# ST_LINK_V2-1.net
KiCad netlist of a schematic drawn in Altium Designer
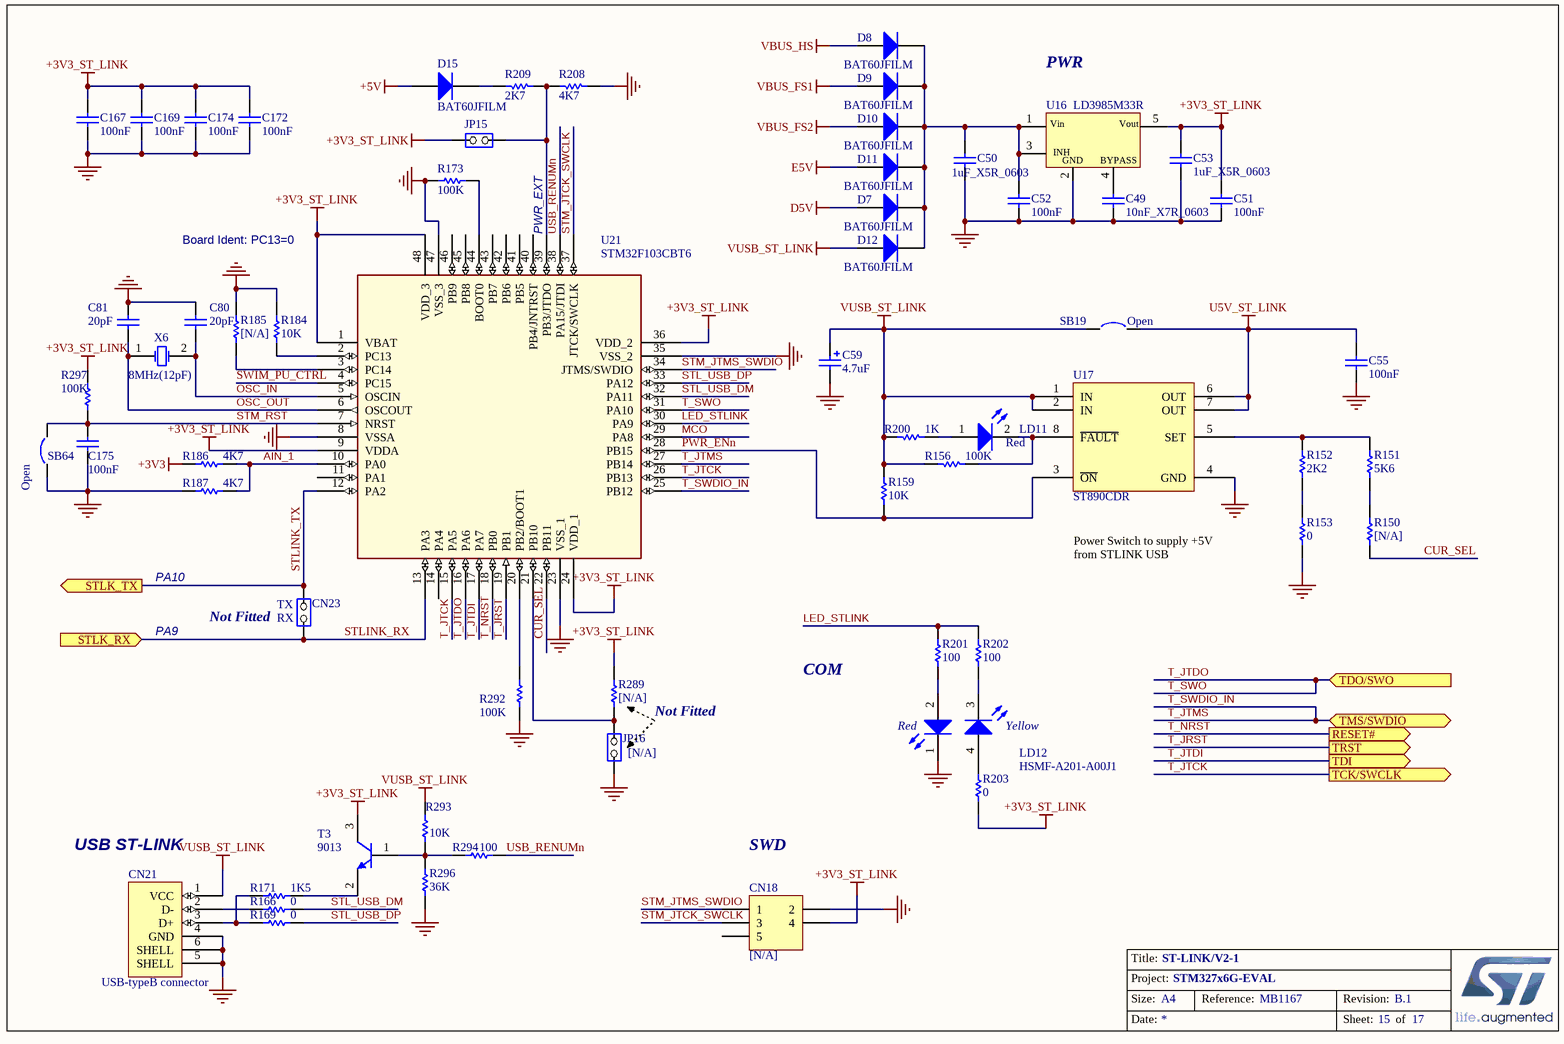
[diagram p0: ST_LINK_V2-1.SCHDOC]

(export (version "E")
  (design (tool "Eeschema 10.0.6"))
  (components
    (comp (ref "C49")
      (value "10nF_X7R_0603")
      (footprint "0603C")
      (description "0603  X7R 10NF")
      (fields (field (name "TOLERANCE") "10%"))
      (libsource (lib "MB963_1") (part "CAP SMD 0603  X7R 10000PF 50V 10%"))
    )
    (comp (ref "C50")
      (value "1uF_X5R_0603")
      (footprint "0603C")
      (description "0603  X5R 1µF")
      (fields (field (name "TOLERANCE") "10%"))
      (libsource (lib "MB963_1") (part "CAP SMD 0603  X5R 1µF 25V 10%"))
    )
    (comp (ref "C51")
      (value "100nF")
      (footprint "0603C")
      (description "Capacitor 0402 / 0603 / 0805")
      (libsource (lib "MCD_TOOLS") (part "Capacitor_ST"))
    )
    (comp (ref "C52")
      (value "100nF")
      (footprint "0603C")
      (description "Capacitor 0402 / 0603 / 0805")
      (libsource (lib "MCD_TOOLS") (part "Capacitor_ST"))
    )
    (comp (ref "C53")
      (value "1uF_X5R_0603")
      (footprint "0603C")
      (description "0603  X5R 1µF")
      (fields (field (name "TOLERANCE") "10%"))
      (libsource (lib "MB963_1") (part "CAP SMD 0603  X5R 1µF 25V 10%"))
    )
    (comp (ref "C55")
      (value "100nF")
      (footprint "0603C")
      (description "Capacitor 0402 / 0603 / 0805")
      (libsource (lib "MCD_TOOLS") (part "Capacitor_ST"))
    )
    (comp (ref "C59")
      (value "4.7uF")
      (footprint "TAN-A")
      (description "Polarized Capacitor (Radial)")
      (fields (field (name "PUBLISHER") "Altium Limited"))
      (libsource (lib "*") (part "Cap Pol1"))
    )
    (comp (ref "C80")
      (value "20pF")
      (footprint "0603C")
      (description "Capacitor 0402 / 0603 / 0805")
      (libsource (lib "MCD_TOOLS") (part "Capacitor_ST"))
    )
    (comp (ref "C81")
      (value "20pF")
      (footprint "0603C")
      (description "Capacitor 0402 / 0603 / 0805")
      (libsource (lib "MCD_TOOLS") (part "Capacitor_ST"))
    )
    (comp (ref "C167")
      (value "100nF")
      (footprint "0603C")
      (description "Capacitor 0402 / 0603 / 0805")
      (libsource (lib "MCD_TOOLS") (part "Capacitor_ST"))
    )
    (comp (ref "C169")
      (value "100nF")
      (footprint "0603C")
      (description "Capacitor 0402 / 0603 / 0805")
      (libsource (lib "MCD_TOOLS") (part "Capacitor_ST"))
    )
    (comp (ref "C172")
      (value "100nF")
      (footprint "0603C")
      (description "Capacitor 0402 / 0603 / 0805")
      (libsource (lib "MCD_TOOLS") (part "Capacitor_ST"))
    )
    (comp (ref "C174")
      (value "100nF")
      (footprint "0603C")
      (description "Capacitor 0402 / 0603 / 0805")
      (libsource (lib "MCD_TOOLS") (part "Capacitor_ST"))
    )
    (comp (ref "C175")
      (value "100nF")
      (footprint "0603C")
      (description "Capacitor 0402 / 0603 / 0805")
      (libsource (lib "MCD_TOOLS") (part "Capacitor_ST"))
    )
    (comp (ref "CN18")
      (value "[N/A]")
      (footprint "HDR_2X3-1_2R54-6")
      (description "Header, 3-Pin, Dual row")
      (fields (field (name "PUBLISHER") "Altium Limited"))
      (libsource (lib "Miscellaneous Connectors") (part "Header 3X2"))
    )
    (comp (ref "CN21")
      (value "USB-typeB connector")
      (footprint "USB-B")
      (libsource (lib "mb1045") (part "USB-typeB connector"))
    )
    (comp (ref "CN23") (value "~") (footprint "SIP2") (libsource (lib "MCD_TOOLS") (part "JP2")))
    (comp (ref "D7")
      (value "BAT60JFILM")
      (footprint "SOD-323")
      (libsource (lib "MCD_TOOLS") (part "BAT60JFILM"))
    )
    (comp (ref "D8")
      (value "BAT60JFILM")
      (footprint "SOD-323")
      (libsource (lib "MCD_TOOLS") (part "BAT60JFILM"))
    )
    (comp (ref "D9")
      (value "BAT60JFILM")
      (footprint "SOD-323")
      (libsource (lib "MCD_TOOLS") (part "BAT60JFILM"))
    )
    (comp (ref "D10")
      (value "BAT60JFILM")
      (footprint "SOD-323")
      (libsource (lib "MCD_TOOLS") (part "BAT60JFILM"))
    )
    (comp (ref "D11")
      (value "BAT60JFILM")
      (footprint "SOD-323")
      (libsource (lib "MCD_TOOLS") (part "BAT60JFILM"))
    )
    (comp (ref "D12")
      (value "BAT60JFILM")
      (footprint "SOD-323")
      (libsource (lib "MCD_TOOLS") (part "BAT60JFILM"))
    )
    (comp (ref "D15")
      (value "BAT60JFILM")
      (footprint "SOD-323")
      (description "Default Diode")
      (fields (field (name "PUBLISHER") "Altium Limited"))
      (libsource (lib "MB1144_1") (part "Diode"))
    )
    (comp (ref "JP15") (value "~") (footprint "SIP2") (libsource (lib "*") (part "JP2")))
    (comp (ref "JP16") (value "[N/A]") (footprint "SIP2") (libsource (lib "*") (part "JP2")))
    (comp (ref "LD11")
      (value "Red")
      (footprint "0603D")
      (description "Typical RED, GREEN, YELLOW, AMBER GaAs LED")
      (fields (field (name "PUBLISHER") "Altium Limited"))
      (libsource (lib "Miscellaneous Devices") (part "LED2"))
    )
    (comp (ref "LD12")
      (value "HSMF-A201-A00J1")
      (footprint "LED2_3528")
      (libsource (lib "MB819") (part "HSMF-A201-A00J1"))
    )
    (comp (ref "R150")
      (value "[N/A]")
      (footprint "0603R")
      (description "Resistor")
      (fields (field (name "PUBLISHER") "Altium Limited"))
      (libsource (lib "") (part "Res1_2"))
    )
    (comp (ref "R151")
      (value "5K6")
      (footprint "0402R")
      (description "Resistor 0402 or 0603 or 0805")
      (libsource (lib "MCD_TOOLS") (part "Resistor_ST"))
    )
    (comp (ref "R152")
      (value "2K2")
      (footprint "0402R")
      (description "Resistor 0402 or 0603 or 0805")
      (libsource (lib "MCD_TOOLS") (part "Resistor_ST"))
    )
    (comp (ref "R153")
      (value "0")
      (footprint "0603R")
      (description "Resistor")
      (fields (field (name "PUBLISHER") "Altium Limited"))
      (libsource (lib "") (part "Res1_2"))
    )
    (comp (ref "R156")
      (value "100K")
      (footprint "0603R")
      (description "Resistor")
      (fields (field (name "PUBLISHER") "Altium Limited"))
      (libsource (lib "*") (part "Res1"))
    )
    (comp (ref "R159")
      (value "10K")
      (footprint "0402R")
      (description "Resistor 0402 or 0603 or 0805")
      (libsource (lib "MCD_TOOLS") (part "Resistor_ST"))
    )
    (comp (ref "R166")
      (value "0")
      (footprint "0603R")
      (description "Resistor 0402 or 0603 or 0805")
      (libsource (lib "") (part "Res1_1"))
    )
    (comp (ref "R169")
      (value "0")
      (footprint "0603R")
      (description "Resistor 0402 or 0603 or 0805")
      (libsource (lib "") (part "Res1_1"))
    )
    (comp (ref "R171")
      (value "1K5")
      (footprint "0603R")
      (description "Resistor 0402 or 0603 or 0805")
      (libsource (lib "") (part "Res1_1"))
    )
    (comp (ref "R173")
      (value "100K")
      (footprint "0603R")
      (description "Resistor 0402 or 0603 or 0805")
      (libsource (lib "") (part "Res1_1"))
    )
    (comp (ref "R184")
      (value "10K")
      (footprint "0603R")
      (description "Resistor 0402 or 0603 or 0805")
      (libsource (lib "") (part "Res1_1"))
    )
    (comp (ref "R185")
      (value "[N/A]")
      (footprint "0603R")
      (description "Resistor 0402 or 0603 or 0805")
      (libsource (lib "") (part "Res1_1"))
    )
    (comp (ref "R186")
      (value "4K7")
      (footprint "0603R")
      (description "Resistor 0402 or 0603 or 0805")
      (libsource (lib "") (part "Res1_1"))
    )
    (comp (ref "R187")
      (value "4K7")
      (footprint "0603R")
      (description "Resistor 0402 or 0603 or 0805")
      (libsource (lib "") (part "Res1_1"))
    )
    (comp (ref "R200")
      (value "1K")
      (footprint "0603R")
      (description "Resistor")
      (fields (field (name "PUBLISHER") "Altium Limited"))
      (libsource (lib "*") (part "Res1"))
    )
    (comp (ref "R201")
      (value "100")
      (footprint "0603R")
      (description "Resistor")
      (fields (field (name "PUBLISHER") "Altium Limited"))
      (libsource (lib "") (part "Res1_2"))
    )
    (comp (ref "R202")
      (value "100")
      (footprint "0603R")
      (description "Resistor")
      (fields (field (name "PUBLISHER") "Altium Limited"))
      (libsource (lib "") (part "Res1_2"))
    )
    (comp (ref "R203")
      (value "0")
      (footprint "0603R")
      (description "Resistor")
      (fields (field (name "PUBLISHER") "Altium Limited"))
      (libsource (lib "") (part "Res1_2"))
    )
    (comp (ref "R208")
      (value "4K7")
      (footprint "0603R")
      (description "Resistor")
      (fields (field (name "PUBLISHER") "Altium Limited"))
      (libsource (lib "Miscellaneous Devices") (part "Res1"))
    )
    (comp (ref "R209")
      (value "2K7")
      (footprint "0603R")
      (description "Resistor")
      (fields (field (name "PUBLISHER") "Altium Limited"))
      (libsource (lib "Miscellaneous Devices") (part "Res1"))
    )
    (comp (ref "R289")
      (value "[N/A]")
      (footprint "0603R")
      (description "Resistor")
      (fields (field (name "PUBLISHER") "Altium Limited"))
      (libsource (lib "") (part "Res1_2"))
    )
    (comp (ref "R292")
      (value "100K")
      (footprint "0603R")
      (description "Resistor 0402 or 0603 or 0805")
      (libsource (lib "") (part "Res1_1"))
    )
    (comp (ref "R293")
      (value "10K")
      (footprint "0603R")
      (description "Resistor")
      (fields (field (name "PUBLISHER") "Altium Limited"))
      (libsource (lib "") (part "Res1_2"))
    )
    (comp (ref "R294")
      (value "100")
      (footprint "0603R")
      (description "Resistor 0402 or 0603 or 0805")
      (libsource (lib "") (part "Res1_1"))
    )
    (comp (ref "R296")
      (value "36K")
      (footprint "0603R")
      (description "Resistor")
      (fields (field (name "PUBLISHER") "Altium Limited"))
      (libsource (lib "") (part "Res1_2"))
    )
    (comp (ref "R297")
      (value "100K")
      (footprint "0603R")
      (description "Resistor 0402 or 0603 or 0805")
      (libsource (lib "") (part "Res1_1"))
    )
    (comp (ref "SB19")
      (value "Open")
      (footprint "SB_0603")
      (description "Circuit Breaker")
      (fields (field (name "PUBLISHER") "Altium Limited"))
      (libsource (lib "MB1167") (part "Circuit Breaker"))
    )
    (comp (ref "SB64")
      (value "Open")
      (footprint "SB_0603")
      (description "Circuit Breaker")
      (fields (field (name "PUBLISHER") "Altium Limited"))
      (libsource (lib "MB1167") (part "Circuit Breaker"))
    )
    (comp (ref "T3")
      (value "9013")
      (footprint "SOT-23")
      (description "NPN Bipolar Transistor")
      (fields (field (name "PUBLISHER") "Altium Limited"))
      (libsource (lib "MB1167") (part "NPN"))
    )
    (comp (ref "U16")
      (value "LD3985M33R")
      (footprint "SOT23-5")
      (description "Ultra low drop-low noise BiCMOS voltage, regulators low ESR capacitors compatible")
      (libsource (lib "MCD_TOOLS") (part "LD3985M33R"))
    )
    (comp (ref "U17")
      (value "ST890CDR")
      (footprint "SOIC8_1R27_4R9X6")
      (libsource (lib "MB1167") (part "ST890CDR"))
    )
    (comp (ref "U21")
      (value "STM32F103CBT6")
      (footprint "LQFP48_0R5_9X9")
      (description "Medium-density performance line ARM-based 32-bit MCU with 64KB Flash")
      (libsource (lib "Nucleo_64") (part "STM32F103CBT6"))
    )
    (comp (ref "X6")
      (value "8MHz(12pF)")
      (footprint "XTAL_2SM_12R7X4R7")
      (description "Crystal Oscillator")
      (fields (field (name "PUBLISHER") "Altium Limited"))
      (libsource (lib "MB963_1") (part "XTAL"))
    )
  )
  (nets
    (net (code "1") (name "+3V3") (class "Default")
      (node (ref "R186") (pin "1") (pinfunction "1_1") (pintype "passive"))
    )
    (net (code "2") (name "+3V3_ST_LINK") (class "Default")
      (node (ref "C167") (pin "2") (pinfunction "2_2") (pintype "passive"))
      (node (ref "C169") (pin "2") (pinfunction "2_2") (pintype "passive"))
      (node (ref "C172") (pin "2") (pinfunction "2_2") (pintype "passive"))
      (node (ref "C174") (pin "2") (pinfunction "2_2") (pintype "passive"))
      (node (ref "C51") (pin "2") (pinfunction "2_2") (pintype "passive"))
      (node (ref "C53") (pin "1") (pinfunction "1_1") (pintype "passive"))
      (node (ref "CN18") (pin "4") (pinfunction "4_4") (pintype "passive"))
      (node (ref "JP15") (pin "1") (pinfunction "COMMON_1") (pintype "passive"))
      (node (ref "R203") (pin "2") (pinfunction "2_2") (pintype "passive"))
      (node (ref "R289") (pin "1") (pinfunction "1_1") (pintype "passive"))
      (node (ref "R297") (pin "2") (pinfunction "2_2") (pintype "passive"))
      (node (ref "T3") (pin "3") (pinfunction "C_3") (pintype "passive"))
      (node (ref "U16") (pin "5") (pinfunction "Vout_5") (pintype "passive"))
      (node (ref "U21") (pin "1") (pinfunction "VBAT_1") (pintype "power_in"))
      (node (ref "U21") (pin "24") (pinfunction "VDD_1_24") (pintype "power_in"))
      (node (ref "U21") (pin "36") (pinfunction "VDD_2_36") (pintype "power_in"))
      (node (ref "U21") (pin "48") (pinfunction "VDD_3_48") (pintype "power_in"))
      (node (ref "U21") (pin "9") (pinfunction "VDDA_9") (pintype "power_in"))
    )
    (net (code "3") (name "+5V") (class "Default")
      (node (ref "D15") (pin "1") (pinfunction "A_1") (pintype "passive"))
    )
    (net (code "4") (name "/AIN_1") (class "Default")
      (node (ref "R186") (pin "2") (pinfunction "2_2") (pintype "passive"))
      (node (ref "R187") (pin "2") (pinfunction "2_2") (pintype "passive"))
      (node (ref "U21") (pin "10") (pinfunction "PA0_10") (pintype "bidirectional"))
    )
    (net (code "5") (name "/CUR_SEL") (class "Default")
      (node (ref "R150") (pin "1") (pinfunction "1_1") (pintype "passive"))
      (node (ref "U21") (pin "22") (pinfunction "PB11_22") (pintype "bidirectional"))
    )
    (net (code "6") (name "/LED_STLINK") (class "Default")
      (node (ref "R201") (pin "1") (pinfunction "1_1") (pintype "passive"))
      (node (ref "R202") (pin "1") (pinfunction "1_1") (pintype "passive"))
      (node (ref "U21") (pin "30") (pinfunction "PA9_30") (pintype "bidirectional"))
    )
    (net (code "7") (name "/MCO") (class "Default")
      (node (ref "U21") (pin "29") (pinfunction "PA8_29") (pintype "bidirectional"))
    )
    (net (code "8") (name "/OSC_IN") (class "Default")
      (node (ref "C80") (pin "1") (pinfunction "1_1") (pintype "passive"))
      (node (ref "U21") (pin "5") (pinfunction "OSCIN_5") (pintype "input"))
      (node (ref "X6") (pin "2") (pinfunction "OSC2_2") (pintype "passive"))
    )
    (net (code "9") (name "/OSC_OUT") (class "Default")
      (node (ref "C81") (pin "1") (pinfunction "1_1") (pintype "passive"))
      (node (ref "U21") (pin "6") (pinfunction "OSCOUT_6") (pintype "output"))
      (node (ref "X6") (pin "1") (pinfunction "OSC1_1") (pintype "passive"))
    )
    (net (code "10") (name "/PWR_ENn") (class "Default")
      (node (ref "R159") (pin "2") (pinfunction "2_2") (pintype "passive"))
      (node (ref "U17") (pin "3") (pinfunction "~{ON}_3") (pintype "passive"))
      (node (ref "U21") (pin "28") (pinfunction "PB15_28") (pintype "bidirectional"))
    )
    (net (code "11") (name "/STLINK_RX") (class "Default")
      (node (ref "CN23") (pin "1") (pinfunction "COMMON_1") (pintype "passive"))
      (node (ref "U21") (pin "13") (pinfunction "PA3_13") (pintype "bidirectional"))
    )
    (net (code "12") (name "/STLINK_TX") (class "Default")
      (node (ref "CN23") (pin "2") (pinfunction "NO_2") (pintype "passive"))
      (node (ref "U21") (pin "12") (pinfunction "PA2_12") (pintype "bidirectional"))
    )
    (net (code "13") (name "/STL_USB_DM") (class "Default")
      (node (ref "R166") (pin "2") (pinfunction "2_2") (pintype "passive"))
      (node (ref "U21") (pin "32") (pinfunction "PA11_32") (pintype "bidirectional"))
    )
    (net (code "14") (name "/STL_USB_DP") (class "Default")
      (node (ref "R169") (pin "2") (pinfunction "2_2") (pintype "passive"))
      (node (ref "U21") (pin "33") (pinfunction "PA12_33") (pintype "bidirectional"))
    )
    (net (code "15") (name "/STM_JTCK_SWCLK") (class "Default")
      (node (ref "CN18") (pin "3") (pinfunction "3_3") (pintype "passive"))
      (node (ref "U21") (pin "37") (pinfunction "JTCK/SWCLK_37") (pintype "bidirectional"))
    )
    (net (code "16") (name "/STM_JTMS_SWDIO") (class "Default")
      (node (ref "CN18") (pin "1") (pinfunction "1_1") (pintype "passive"))
      (node (ref "U21") (pin "34") (pinfunction "JTMS/SWDIO_34") (pintype "bidirectional"))
    )
    (net (code "17") (name "/STM_RST") (class "Default")
      (node (ref "C175") (pin "2") (pinfunction "2_2") (pintype "passive"))
      (node (ref "R297") (pin "1") (pinfunction "1_1") (pintype "passive"))
      (node (ref "SB64") (pin "2") (pinfunction "2_2") (pintype "passive"))
      (node (ref "U21") (pin "7") (pinfunction "NRST_7") (pintype "input"))
    )
    (net (code "18") (name "/SWIM_PU_CTRL") (class "Default")
      (node (ref "U21") (pin "4") (pinfunction "PC15_4") (pintype "bidirectional"))
    )
    (net (code "19") (name "/T_JRST") (class "Default")
      (node (ref "U21") (pin "19") (pinfunction "PB1_19") (pintype "input"))
    )
    (net (code "20") (name "/T_JTCK") (class "Default")
      (node (ref "U21") (pin "15") (pinfunction "PA5_15") (pintype "bidirectional"))
      (node (ref "U21") (pin "26") (pinfunction "PB13_26") (pintype "bidirectional"))
    )
    (net (code "21") (name "/T_JTDI") (class "Default")
      (node (ref "U21") (pin "17") (pinfunction "PA7_17") (pintype "bidirectional"))
    )
    (net (code "22") (name "/T_JTDO") (class "Default")
      (node (ref "U21") (pin "16") (pinfunction "PA6_16") (pintype "bidirectional"))
      (node (ref "U21") (pin "31") (pinfunction "PA10_31") (pintype "bidirectional"))
    )
    (net (code "23") (name "/T_JTMS") (class "Default")
      (node (ref "U21") (pin "25") (pinfunction "PB12_25") (pintype "bidirectional"))
      (node (ref "U21") (pin "27") (pinfunction "PB14_27") (pintype "bidirectional"))
    )
    (net (code "24") (name "/T_NRST") (class "Default")
      (node (ref "U21") (pin "18") (pinfunction "PB0_18") (pintype "bidirectional"))
    )
    (net (code "25") (name "/USB_RENUMn") (class "Default")
      (node (ref "R294") (pin "2") (pinfunction "2_2") (pintype "passive"))
      (node (ref "U21") (pin "38") (pinfunction "PA15/JTDI_38") (pintype "bidirectional"))
    )
    (net (code "26") (name "D5V") (class "Default")
      (node (ref "D7") (pin "1") (pinfunction "A_1") (pintype "passive"))
    )
    (net (code "27") (name "E5V") (class "Default")
      (node (ref "D11") (pin "1") (pinfunction "A_1") (pintype "passive"))
    )
    (net (code "28") (name "GND") (class "Default")
      (node (ref "C167") (pin "1") (pinfunction "1_1") (pintype "passive"))
      (node (ref "C169") (pin "1") (pinfunction "1_1") (pintype "passive"))
      (node (ref "C172") (pin "1") (pinfunction "1_1") (pintype "passive"))
      (node (ref "C174") (pin "1") (pinfunction "1_1") (pintype "passive"))
      (node (ref "C175") (pin "1") (pinfunction "1_1") (pintype "passive"))
      (node (ref "C49") (pin "1") (pinfunction "1_1") (pintype "passive"))
      (node (ref "C50") (pin "1") (pinfunction "1_1") (pintype "passive"))
      (node (ref "C51") (pin "1") (pinfunction "1_1") (pintype "passive"))
      (node (ref "C52") (pin "1") (pinfunction "1_1") (pintype "passive"))
      (node (ref "C53") (pin "2") (pinfunction "2_2") (pintype "passive"))
      (node (ref "C55") (pin "1") (pinfunction "1_1") (pintype "passive"))
      (node (ref "C59") (pin "2") (pinfunction "2_2") (pintype "passive"))
      (node (ref "C80") (pin "2") (pinfunction "2_2") (pintype "passive"))
      (node (ref "C81") (pin "2") (pinfunction "2_2") (pintype "passive"))
      (node (ref "CN18") (pin "2") (pinfunction "2_2") (pintype "passive"))
      (node (ref "CN21") (pin "4") (pinfunction "GND_4") (pintype "passive"))
      (node (ref "CN21") (pin "5") (pinfunction "SHELL_5") (pintype "power_in"))
      (node (ref "CN21") (pin "6") (pinfunction "SHELL_6") (pintype "power_in"))
      (node (ref "JP16") (pin "1") (pinfunction "COMMON_1") (pintype "passive"))
      (node (ref "LD12") (pin "1") (pinfunction "RED_cathode_1") (pintype "passive"))
      (node (ref "R153") (pin "1") (pinfunction "1_1") (pintype "passive"))
      (node (ref "R173") (pin "1") (pinfunction "1_1") (pintype "passive"))
      (node (ref "R184") (pin "1") (pinfunction "1_1") (pintype "passive"))
      (node (ref "R185") (pin "1") (pinfunction "1_1") (pintype "passive"))
      (node (ref "R187") (pin "1") (pinfunction "1_1") (pintype "passive"))
      (node (ref "R208") (pin "2") (pinfunction "2_2") (pintype "passive"))
      (node (ref "R292") (pin "1") (pinfunction "1_1") (pintype "passive"))
      (node (ref "R296") (pin "1") (pinfunction "1_1") (pintype "passive"))
      (node (ref "SB64") (pin "1") (pinfunction "1_1") (pintype "passive"))
      (node (ref "U16") (pin "2") (pinfunction "GND_2") (pintype "passive"))
      (node (ref "U17") (pin "4") (pinfunction "GND_4") (pintype "passive"))
      (node (ref "U21") (pin "23") (pinfunction "VSS_1_23") (pintype "power_in"))
      (node (ref "U21") (pin "35") (pinfunction "VSS_2_35") (pintype "power_in"))
      (node (ref "U21") (pin "47") (pinfunction "VSS_3_47") (pintype "power_in"))
      (node (ref "U21") (pin "8") (pinfunction "VSSA_8") (pintype "power_in"))
    )
    (net (code "29") (name "Net-(CN21-D+)") (class "Default")
      (node (ref "CN21") (pin "3") (pinfunction "D+_3") (pintype "bidirectional"))
      (node (ref "R169") (pin "1") (pinfunction "1_1") (pintype "passive"))
      (node (ref "R171") (pin "1") (pinfunction "1_1") (pintype "passive"))
    )
    (net (code "30") (name "Net-(CN21-D-)") (class "Default")
      (node (ref "CN21") (pin "2") (pinfunction "D-_2") (pintype "bidirectional"))
      (node (ref "R166") (pin "1") (pinfunction "1_1") (pintype "passive"))
    )
    (net (code "31") (name "Net-(D10-K)") (class "Default")
      (node (ref "C50") (pin "2") (pinfunction "2_2") (pintype "passive"))
      (node (ref "C52") (pin "2") (pinfunction "2_2") (pintype "passive"))
      (node (ref "D10") (pin "2") (pinfunction "K_2") (pintype "passive"))
      (node (ref "D11") (pin "2") (pinfunction "K_2") (pintype "passive"))
      (node (ref "D12") (pin "2") (pinfunction "K_2") (pintype "passive"))
      (node (ref "D7") (pin "2") (pinfunction "K_2") (pintype "passive"))
      (node (ref "D8") (pin "2") (pinfunction "K_2") (pintype "passive"))
      (node (ref "D9") (pin "2") (pinfunction "K_2") (pintype "passive"))
      (node (ref "U16") (pin "1") (pinfunction "Vin_1") (pintype "passive"))
      (node (ref "U16") (pin "3") (pinfunction "CE_3") (pintype "passive"))
    )
    (net (code "32") (name "Net-(D15-K)") (class "Default")
      (node (ref "D15") (pin "2") (pinfunction "K_2") (pintype "passive"))
      (node (ref "R209") (pin "1") (pinfunction "1_1") (pintype "passive"))
    )
    (net (code "33") (name "Net-(JP15-NO)") (class "Default")
      (node (ref "JP15") (pin "2") (pinfunction "NO_2") (pintype "passive"))
      (node (ref "R208") (pin "1") (pinfunction "1_1") (pintype "passive"))
      (node (ref "R209") (pin "2") (pinfunction "2_2") (pintype "passive"))
      (node (ref "U21") (pin "39") (pinfunction "PB3/JTDO_39") (pintype "bidirectional"))
    )
    (net (code "34") (name "Net-(JP16-NO)") (class "Default")
      (node (ref "JP16") (pin "2") (pinfunction "NO_2") (pintype "passive"))
      (node (ref "R289") (pin "2") (pinfunction "2_2") (pintype "passive"))
      (node (ref "U21") (pin "21") (pinfunction "PB10_21") (pintype "bidirectional"))
    )
    (net (code "35") (name "Net-(LD11-A)") (class "Default")
      (node (ref "LD11") (pin "1") (pinfunction "A_1") (pintype "passive"))
      (node (ref "R200") (pin "2") (pinfunction "2_2") (pintype "passive"))
    )
    (net (code "36") (name "Net-(LD11-K)") (class "Default")
      (node (ref "LD11") (pin "2") (pinfunction "K_2") (pintype "passive"))
      (node (ref "R156") (pin "2") (pinfunction "2_2") (pintype "passive"))
      (node (ref "U17") (pin "8") (pinfunction "~{FAULT}_8") (pintype "passive"))
    )
    (net (code "37") (name "Net-(LD12-Red_anode)") (class "Default")
      (node (ref "LD12") (pin "2") (pinfunction "Red_anode_2") (pintype "passive"))
      (node (ref "R201") (pin "2") (pinfunction "2_2") (pintype "passive"))
    )
    (net (code "38") (name "Net-(LD12-YellowGreen_anode)") (class "Default")
      (node (ref "LD12") (pin "4") (pinfunction "YellowGreen_anode_4") (pintype "passive"))
      (node (ref "R203") (pin "1") (pinfunction "1_1") (pintype "passive"))
    )
    (net (code "39") (name "Net-(LD12-YellowGreen_cathode)") (class "Default")
      (node (ref "LD12") (pin "3") (pinfunction "YellowGreen_cathode_3") (pintype "passive"))
      (node (ref "R202") (pin "2") (pinfunction "2_2") (pintype "passive"))
    )
    (net (code "40") (name "Net-(R150-Pad2)") (class "Default")
      (node (ref "R150") (pin "2") (pinfunction "2_2") (pintype "passive"))
      (node (ref "R151") (pin "1") (pinfunction "1_1") (pintype "passive"))
    )
    (net (code "41") (name "Net-(R152-Pad1)") (class "Default")
      (node (ref "R152") (pin "1") (pinfunction "1_1") (pintype "passive"))
      (node (ref "R153") (pin "2") (pinfunction "2_2") (pintype "passive"))
    )
    (net (code "42") (name "Net-(T3-B)") (class "Default")
      (node (ref "R293") (pin "1") (pinfunction "1_1") (pintype "passive"))
      (node (ref "R294") (pin "1") (pinfunction "1_1") (pintype "passive"))
      (node (ref "R296") (pin "2") (pinfunction "2_2") (pintype "passive"))
      (node (ref "T3") (pin "1") (pinfunction "B_1") (pintype "passive"))
    )
    (net (code "43") (name "Net-(T3-E)") (class "Default")
      (node (ref "R171") (pin "2") (pinfunction "2_2") (pintype "passive"))
      (node (ref "T3") (pin "2") (pinfunction "E_2") (pintype "passive"))
    )
    (net (code "44") (name "Net-(U16-BYPASS)") (class "Default")
      (node (ref "C49") (pin "2") (pinfunction "2_2") (pintype "passive"))
      (node (ref "U16") (pin "4") (pinfunction "BYPASS_4") (pintype "passive"))
    )
    (net (code "45") (name "Net-(U17-SET)") (class "Default")
      (node (ref "R151") (pin "2") (pinfunction "2_2") (pintype "passive"))
      (node (ref "R152") (pin "2") (pinfunction "2_2") (pintype "passive"))
      (node (ref "U17") (pin "5") (pinfunction "SET_5") (pintype "passive"))
    )
    (net (code "46") (name "Net-(U21-BOOT0)") (class "Default")
      (node (ref "R173") (pin "2") (pinfunction "2_2") (pintype "passive"))
      (node (ref "U21") (pin "44") (pinfunction "BOOT0_44") (pintype "bidirectional"))
    )
    (net (code "47") (name "Net-(U21-PB2{slash}BOOT1)") (class "Default")
      (node (ref "R292") (pin "2") (pinfunction "2_2") (pintype "passive"))
      (node (ref "U21") (pin "20") (pinfunction "PB2/BOOT1_20") (pintype "bidirectional"))
    )
    (net (code "48") (name "Net-(U21-PC13)") (class "Default")
      (node (ref "R184") (pin "2") (pinfunction "2_2") (pintype "passive"))
      (node (ref "U21") (pin "2") (pinfunction "PC13_2") (pintype "bidirectional"))
    )
    (net (code "49") (name "Net-(U21-PC14)") (class "Default")
      (node (ref "R185") (pin "2") (pinfunction "2_2") (pintype "passive"))
      (node (ref "U21") (pin "3") (pinfunction "PC14_3") (pintype "bidirectional"))
    )
    (net (code "50") (name "U5V_ST_LINK") (class "Default")
      (node (ref "C55") (pin "2") (pinfunction "2_2") (pintype "passive"))
      (node (ref "SB19") (pin "2") (pinfunction "2_2") (pintype "passive"))
      (node (ref "U17") (pin "6") (pinfunction "OUT_6") (pintype "passive"))
      (node (ref "U17") (pin "7") (pinfunction "OUT_7") (pintype "passive"))
    )
    (net (code "51") (name "VBUS_FS1") (class "Default")
      (node (ref "D9") (pin "1") (pinfunction "A_1") (pintype "passive"))
    )
    (net (code "52") (name "VBUS_FS2") (class "Default")
      (node (ref "D10") (pin "1") (pinfunction "A_1") (pintype "passive"))
    )
    (net (code "53") (name "VBUS_HS") (class "Default")
      (node (ref "D8") (pin "1") (pinfunction "A_1") (pintype "passive"))
    )
    (net (code "54") (name "VUSB_ST_LINK") (class "Default")
      (node (ref "C59") (pin "1") (pinfunction "1_1") (pintype "passive"))
      (node (ref "CN21") (pin "1") (pinfunction "VCC_1") (pintype "bidirectional"))
      (node (ref "D12") (pin "1") (pinfunction "A_1") (pintype "passive"))
      (node (ref "R156") (pin "1") (pinfunction "1_1") (pintype "passive"))
      (node (ref "R159") (pin "1") (pinfunction "1_1") (pintype "passive"))
      (node (ref "R200") (pin "1") (pinfunction "1_1") (pintype "passive"))
      (node (ref "R293") (pin "2") (pinfunction "2_2") (pintype "passive"))
      (node (ref "SB19") (pin "1") (pinfunction "1_1") (pintype "passive"))
      (node (ref "U17") (pin "1") (pinfunction "IN_1") (pintype "passive"))
      (node (ref "U17") (pin "2") (pinfunction "IN_2") (pintype "passive"))
    )
    (net (code "55") (name "unconnected-(CN18-Pad5)") (class "Default")
      (node (ref "CN18") (pin "5") (pinfunction "5_5") (pintype "passive"))
    )
    (net (code "56") (name "unconnected-(U21-PA1-Pad11)") (class "Default")
      (node (ref "U21") (pin "11") (pinfunction "PA1_11") (pintype "bidirectional"))
    )
    (net (code "57") (name "unconnected-(U21-PA4-Pad14)") (class "Default")
      (node (ref "U21") (pin "14") (pinfunction "PA4_14") (pintype "bidirectional"))
    )
    (net (code "58") (name "unconnected-(U21-PB4{slash}JNTRST-Pad40)") (class "Default")
      (node (ref "U21") (pin "40") (pinfunction "PB4/JNTRST_40") (pintype "bidirectional"))
    )
    (net (code "59") (name "unconnected-(U21-PB5-Pad41)") (class "Default")
      (node (ref "U21") (pin "41") (pinfunction "PB5_41") (pintype "bidirectional"))
    )
    (net (code "60") (name "unconnected-(U21-PB6-Pad42)") (class "Default")
      (node (ref "U21") (pin "42") (pinfunction "PB6_42") (pintype "bidirectional"))
    )
    (net (code "61") (name "unconnected-(U21-PB7-Pad43)") (class "Default")
      (node (ref "U21") (pin "43") (pinfunction "PB7_43") (pintype "bidirectional"))
    )
    (net (code "62") (name "unconnected-(U21-PB8-Pad45)") (class "Default")
      (node (ref "U21") (pin "45") (pinfunction "PB8_45") (pintype "bidirectional"))
    )
    (net (code "63") (name "unconnected-(U21-PB9-Pad46)") (class "Default")
      (node (ref "U21") (pin "46") (pinfunction "PB9_46") (pintype "bidirectional"))
    )
  )
)
